# Main.net
KiCad netlist of a schematic drawn in Altium Designer
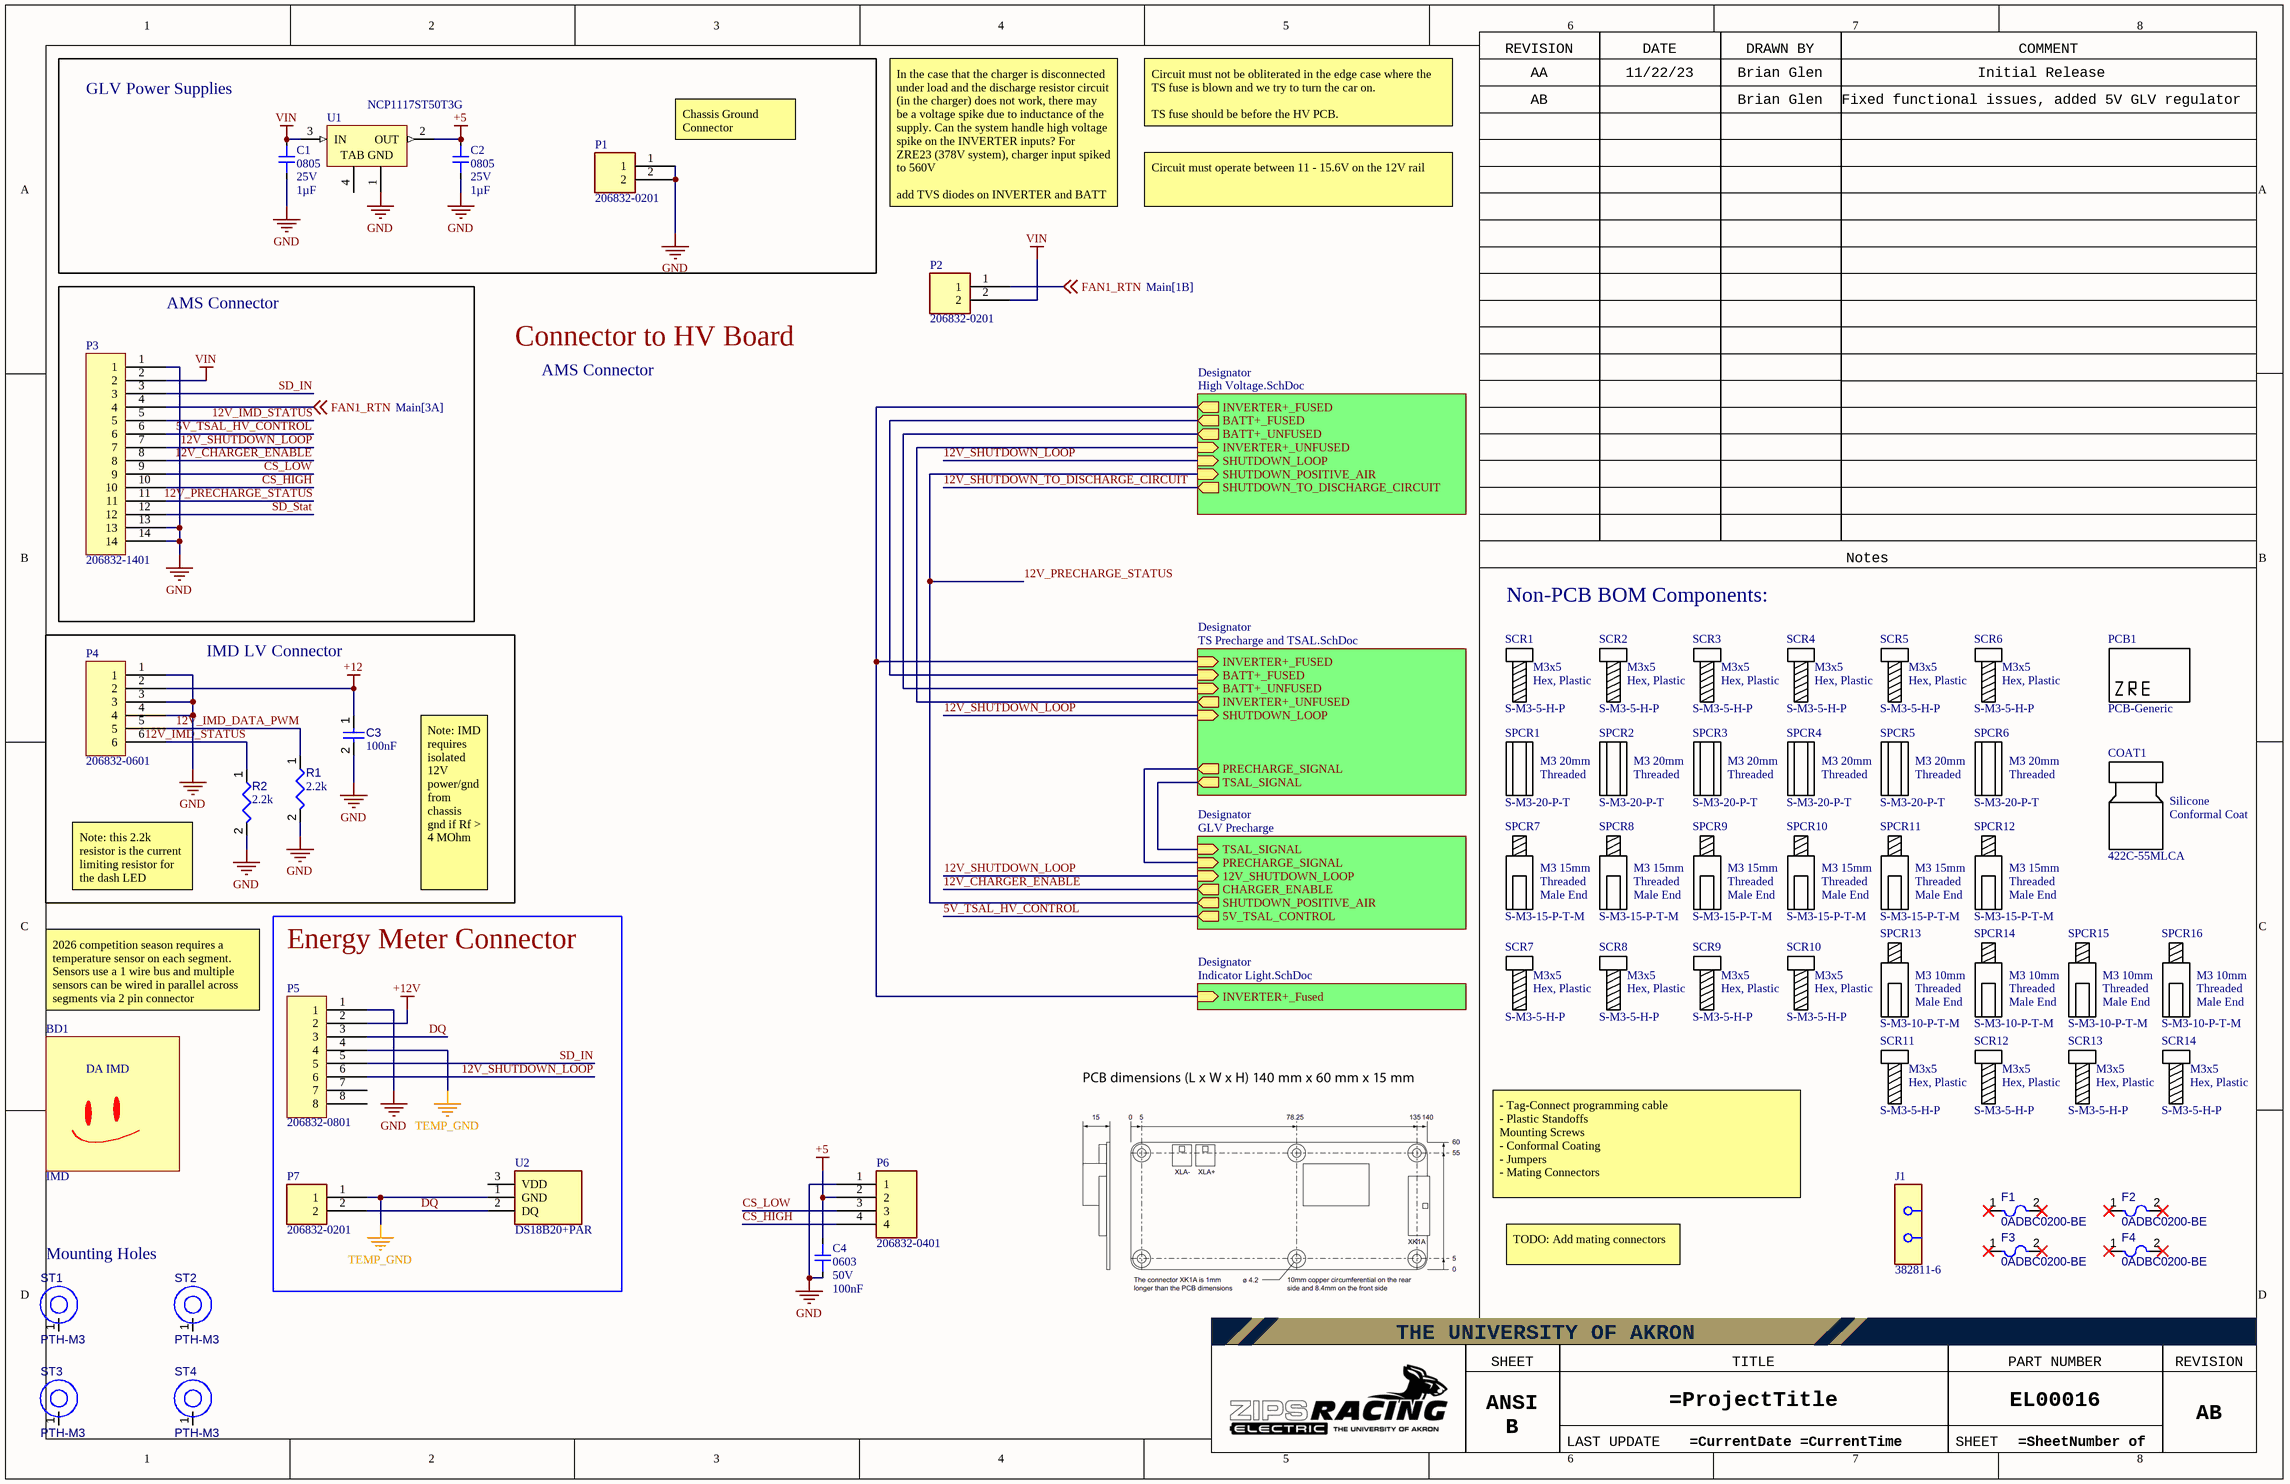
[diagram p0: Main.SchDoc]

(export (version "E")
  (design (tool "Eeschema 10.0.6"))
  (components
    (comp (ref "BD1")
      (value "IMD")
      (footprint "IMD-Footprint-1")
      (description "IMD for the CAR")
      (libsource (lib "Zips Racing Electric") (part "IMD-Symbol-1"))
    )
    (comp (ref "C1")
      (value "1µF")
      (footprint "0805")
      (description "Capacitor, 0805")
      (fields (field (name "VOLTAGE") "25V") (field (name "Comment") "Capacitor 1uF 0805 25V"))
      (libsource (lib "Zips Racing Electric") (part "CAP-0603"))
    )
    (comp (ref "C2")
      (value "1µF")
      (footprint "0805")
      (description "Capacitor, 0805")
      (fields (field (name "VOLTAGE") "25V") (field (name "Comment") "Capacitor 1uF 0805 25V"))
      (libsource (lib "Zips Racing Electric") (part "CAP-0603"))
    )
    (comp (ref "C3")
      (value "100nF")
      (footprint "CAPC1608X90X40NL10T20")
      (description "Chip Capacitor, 100 nF, +/- 10%, 50 V, 0603 (1608 Metric)")
      (fields (field (name "TOLERANCE") "10%") (field (name "Comment") "Capacitor 100 nF +/-10% 50 V 0603"))
      (libsource (lib "Zips Racing Electric") (part "CAP-NP-2"))
    )
    (comp (ref "C4")
      (value "100nF")
      (footprint "0603")
      (description "Capacitor, 0603, 5%")
      (fields (field (name "VOLTAGE") "50V") (field (name "Comment") "Capacitor 100nF 0603 5%"))
      (libsource (lib "Zips Racing Electric") (part "CAP-0603"))
    )
    (comp (ref "COAT1")
      (value "422C-55MLCA")
      (libsource (lib "Zips Racing Electric") (part "422C-55MLCA-Symbol-1"))
    )
    (comp (ref "F1")
      (value "0ADBC0200-BE")
      (description "Electric Fuse, Fast Blow, 0.2A, 1000VAC, 1000VDC, 0.2A (IR), Inline/holder, 6x32mm")
      (libsource (lib "Zips Racing Electric") (part "FUSE-2"))
    )
    (comp (ref "F2")
      (value "0ADBC0200-BE")
      (description "Electric Fuse, Fast Blow, 0.2A, 1000VAC, 1000VDC, 0.2A (IR), Inline/holder, 6x32mm")
      (libsource (lib "Zips Racing Electric") (part "FUSE-2"))
    )
    (comp (ref "F3")
      (value "0ADBC0200-BE")
      (description "Electric Fuse, Fast Blow, 0.2A, 1000VAC, 1000VDC, 0.2A (IR), Inline/holder, 6x32mm")
      (libsource (lib "Zips Racing Electric") (part "FUSE-2"))
    )
    (comp (ref "F4")
      (value "0ADBC0200-BE")
      (description "Electric Fuse, Fast Blow, 0.2A, 1000VAC, 1000VDC, 0.2A (IR), Inline/holder, 6x32mm")
      (libsource (lib "Zips Racing Electric") (part "FUSE-2"))
    )
    (comp (ref "J1")
      (value "382811-6")
      (footprint "FP-382811-6-MFG")
      (description "2-Pin Header Pin Jumper, 0.1\" pitch, Shunts/Jumper Connector")
      (libsource (lib "Zips Racing Electric") (part "9bfe63f1ac6509a30e43ee188490ecc"))
    )
    (comp (ref "P1")
      (value "206832-0201")
      (footprint "FP-206832-0201-MFG")
      (description "Molex, Micro-Fit+, 2 Position, Dual-Row, Header, Male, 3mm Pitch")
      (libsource (lib "Zips Racing Electric") (part "206832-0201"))
    )
    (comp (ref "P2")
      (value "206832-0201")
      (footprint "FP-206832-0201-MFG")
      (description "Molex, Micro-Fit+, 2 Position, Dual-Row, Header, Male, 3mm Pitch")
      (libsource (lib "Zips Racing Electric") (part "206832-0201"))
    )
    (comp (ref "P3")
      (value "206832-1401")
      (footprint "206832-1001-Footprint-1")
      (description "MICRO-FIT Plus Header Assembly Dual Row 10 Position Straight Tin")
      (libsource (lib "Zips Racing Electric") (part "206832-1401-Symbol-1"))
    )
    (comp (ref "P4")
      (value "206832-0601")
      (footprint "FP-206832-0601-MFG")
      (description "Molex, Micro-Fit+, 6 Position, Dual-Row, Header, Male, 3mm Pitch")
      (libsource (lib "Zips Racing Electric") (part "2068320601"))
    )
    (comp (ref "P5")
      (value "206832-0801")
      (footprint "Copy of 206832-1001-Footprint-1")
      (description "MICRO-FIT Plus Header Assembly Dual Row 8 Position Straight Tin")
      (libsource (lib "Zips Racing Electric") (part "206832-0801"))
    )
    (comp (ref "P6")
      (value "206832-0401")
      (footprint "MOLEX_2068320401")
      (libsource (lib "Zips Racing Electric") (part "2068320401-Symbol-1"))
    )
    (comp (ref "P7")
      (value "206832-0201")
      (footprint "FP-206832-0201-MFG")
      (description "Molex, Micro-Fit+, 2 Position, Dual-Row, Header, Male, 3mm Pitch")
      (libsource (lib "Zips Racing Electric") (part "206832-0201"))
    )
    (comp (ref "PCB1")
      (value "PCB-Generic")
      (description "Generic PCB Component for BOM inclusion")
      (libsource (lib "Zips Racing Electric") (part "PCB-Generic-Symbol-1"))
    )
    (comp (ref "R1")
      (value "2.2k")
      (footprint "RESC1608X55X25LL10T15")
      (description "Description Chip Resistor, 2.2 KOhm, +/-1%, 0.1 W, -55 to 155 degC, 0603 (1608 Metric)")
      (fields (field (name "POWER") "100mW") (field (name "TOLERANCE") "1%"))
      (libsource (lib "Zips Racing Electric") (part "RES-2"))
    )
    (comp (ref "R2")
      (value "2.2k")
      (footprint "RESC1608X55X25LL10T15")
      (description "Description Chip Resistor, 2.2 KOhm, +/-1%, 0.1 W, -55 to 155 degC, 0603 (1608 Metric)")
      (fields (field (name "POWER") "100mW") (field (name "TOLERANCE") "1%"))
      (libsource (lib "Zips Racing Electric") (part "RES-2"))
    )
    (comp (ref "SCR1")
      (value "S-M3-5-H-P")
      (description "Generic Screw, M3, 5mm length, Hex Head, Plastic")
      (libsource (lib "Zips Racing Electric") (part "S-M3-5-P-Symbol-1"))
    )
    (comp (ref "SCR2")
      (value "S-M3-5-H-P")
      (description "Generic Screw, M3, 5mm length, Hex Head, Plastic")
      (libsource (lib "Zips Racing Electric") (part "S-M3-5-P-Symbol-1"))
    )
    (comp (ref "SCR3")
      (value "S-M3-5-H-P")
      (description "Generic Screw, M3, 5mm length, Hex Head, Plastic")
      (libsource (lib "Zips Racing Electric") (part "S-M3-5-P-Symbol-1"))
    )
    (comp (ref "SCR4")
      (value "S-M3-5-H-P")
      (description "Generic Screw, M3, 5mm length, Hex Head, Plastic")
      (libsource (lib "Zips Racing Electric") (part "S-M3-5-P-Symbol-1"))
    )
    (comp (ref "SCR5")
      (value "S-M3-5-H-P")
      (description "Generic Screw, M3, 5mm length, Hex Head, Plastic")
      (libsource (lib "Zips Racing Electric") (part "S-M3-5-P-Symbol-1"))
    )
    (comp (ref "SCR6")
      (value "S-M3-5-H-P")
      (description "Generic Screw, M3, 5mm length, Hex Head, Plastic")
      (libsource (lib "Zips Racing Electric") (part "S-M3-5-P-Symbol-1"))
    )
    (comp (ref "SCR7")
      (value "S-M3-5-H-P")
      (description "Generic Screw, M3, 5mm length, Hex Head, Plastic")
      (libsource (lib "Zips Racing Electric") (part "S-M3-5-P-Symbol-1"))
    )
    (comp (ref "SCR8")
      (value "S-M3-5-H-P")
      (description "Generic Screw, M3, 5mm length, Hex Head, Plastic")
      (libsource (lib "Zips Racing Electric") (part "S-M3-5-P-Symbol-1"))
    )
    (comp (ref "SCR9")
      (value "S-M3-5-H-P")
      (description "Generic Screw, M3, 5mm length, Hex Head, Plastic")
      (libsource (lib "Zips Racing Electric") (part "S-M3-5-P-Symbol-1"))
    )
    (comp (ref "SCR10")
      (value "S-M3-5-H-P")
      (description "Generic Screw, M3, 5mm length, Hex Head, Plastic")
      (libsource (lib "Zips Racing Electric") (part "S-M3-5-P-Symbol-1"))
    )
    (comp (ref "SCR11")
      (value "S-M3-5-H-P")
      (description "Generic Screw, M3, 5mm length, Hex Head, Plastic")
      (libsource (lib "Zips Racing Electric") (part "S-M3-5-P-Symbol-1"))
    )
    (comp (ref "SCR12")
      (value "S-M3-5-H-P")
      (description "Generic Screw, M3, 5mm length, Hex Head, Plastic")
      (libsource (lib "Zips Racing Electric") (part "S-M3-5-P-Symbol-1"))
    )
    (comp (ref "SCR13")
      (value "S-M3-5-H-P")
      (description "Generic Screw, M3, 5mm length, Hex Head, Plastic")
      (libsource (lib "Zips Racing Electric") (part "S-M3-5-P-Symbol-1"))
    )
    (comp (ref "SCR14")
      (value "S-M3-5-H-P")
      (description "Generic Screw, M3, 5mm length, Hex Head, Plastic")
      (libsource (lib "Zips Racing Electric") (part "S-M3-5-P-Symbol-1"))
    )
    (comp (ref "SPCR1")
      (value "S-M3-20-P-T")
      (description "Generic M3 Spacer, 10 mm length, plastic, threaded")
      (libsource (lib "") (part "M3_Spacer_10mm_Plastic_Threaded-Symbol-1_2"))
    )
    (comp (ref "SPCR2")
      (value "S-M3-20-P-T")
      (description "Generic M3 Spacer, 10 mm length, plastic, threaded")
      (libsource (lib "") (part "M3_Spacer_10mm_Plastic_Threaded-Symbol-1_2"))
    )
    (comp (ref "SPCR3")
      (value "S-M3-20-P-T")
      (description "Generic M3 Spacer, 10 mm length, plastic, threaded")
      (libsource (lib "") (part "M3_Spacer_10mm_Plastic_Threaded-Symbol-1_2"))
    )
    (comp (ref "SPCR4")
      (value "S-M3-20-P-T")
      (description "Generic M3 Spacer, 10 mm length, plastic, threaded")
      (libsource (lib "") (part "M3_Spacer_10mm_Plastic_Threaded-Symbol-1_2"))
    )
    (comp (ref "SPCR5")
      (value "S-M3-20-P-T")
      (description "Generic M3 Spacer, 10 mm length, plastic, threaded")
      (libsource (lib "") (part "M3_Spacer_10mm_Plastic_Threaded-Symbol-1_2"))
    )
    (comp (ref "SPCR6")
      (value "S-M3-20-P-T")
      (description "Generic M3 Spacer, 10 mm length, plastic, threaded")
      (libsource (lib "") (part "M3_Spacer_10mm_Plastic_Threaded-Symbol-1_2"))
    )
    (comp (ref "SPCR7")
      (value "S-M3-15-P-T-M")
      (description "Generic M3 Spacer, 15 mm length, plastic, threaded, one male end")
      (libsource (lib "Zips Racing Electric") (part "M3_Spacer_10mm_Plastic_Threaded-Symbol-1"))
    )
    (comp (ref "SPCR8")
      (value "S-M3-15-P-T-M")
      (description "Generic M3 Spacer, 15 mm length, plastic, threaded, one male end")
      (libsource (lib "Zips Racing Electric") (part "M3_Spacer_10mm_Plastic_Threaded-Symbol-1"))
    )
    (comp (ref "SPCR9")
      (value "S-M3-15-P-T-M")
      (description "Generic M3 Spacer, 15 mm length, plastic, threaded, one male end")
      (libsource (lib "Zips Racing Electric") (part "M3_Spacer_10mm_Plastic_Threaded-Symbol-1"))
    )
    (comp (ref "SPCR10")
      (value "S-M3-15-P-T-M")
      (description "Generic M3 Spacer, 15 mm length, plastic, threaded, one male end")
      (libsource (lib "Zips Racing Electric") (part "M3_Spacer_10mm_Plastic_Threaded-Symbol-1"))
    )
    (comp (ref "SPCR11")
      (value "S-M3-15-P-T-M")
      (description "Generic M3 Spacer, 15 mm length, plastic, threaded, one male end")
      (libsource (lib "Zips Racing Electric") (part "M3_Spacer_10mm_Plastic_Threaded-Symbol-1"))
    )
    (comp (ref "SPCR12")
      (value "S-M3-15-P-T-M")
      (description "Generic M3 Spacer, 15 mm length, plastic, threaded, one male end")
      (libsource (lib "Zips Racing Electric") (part "M3_Spacer_10mm_Plastic_Threaded-Symbol-1"))
    )
    (comp (ref "SPCR13")
      (value "S-M3-10-P-T-M")
      (description "Generic M3 Spacer, 10 mm length, plastic, threaded, one male end")
      (libsource (lib "") (part "M3_Spacer_10mm_Plastic_Threaded-Symbol-1_1"))
    )
    (comp (ref "SPCR14")
      (value "S-M3-10-P-T-M")
      (description "Generic M3 Spacer, 10 mm length, plastic, threaded, one male end")
      (libsource (lib "") (part "M3_Spacer_10mm_Plastic_Threaded-Symbol-1_1"))
    )
    (comp (ref "SPCR15")
      (value "S-M3-10-P-T-M")
      (description "Generic M3 Spacer, 10 mm length, plastic, threaded, one male end")
      (libsource (lib "") (part "M3_Spacer_10mm_Plastic_Threaded-Symbol-1_1"))
    )
    (comp (ref "SPCR16")
      (value "S-M3-10-P-T-M")
      (description "Generic M3 Spacer, 10 mm length, plastic, threaded, one male end")
      (libsource (lib "") (part "M3_Spacer_10mm_Plastic_Threaded-Symbol-1_1"))
    )
    (comp (ref "ST1")
      (value "PTH-M3")
      (footprint "PTH-M2D5X5")
      (description "M3 Plated Thru-Hole  (3.2mm), 7mm pad, 10 mm keep out zone")
      (libsource (lib "Zips Racing Electric") (part "CMP-00028-00000-1"))
    )
    (comp (ref "ST2")
      (value "PTH-M3")
      (footprint "PTH-M2D5X5")
      (description "M3 Plated Thru-Hole  (3.2mm), 7mm pad, 10 mm keep out zone")
      (libsource (lib "Zips Racing Electric") (part "CMP-00028-00000-1"))
    )
    (comp (ref "ST3")
      (value "PTH-M3")
      (footprint "PTH-M2D5X5")
      (description "M3 Plated Thru-Hole  (3.2mm), 7mm pad, 10 mm keep out zone")
      (libsource (lib "Zips Racing Electric") (part "CMP-00028-00000-1"))
    )
    (comp (ref "ST4")
      (value "PTH-M3")
      (footprint "PTH-M2D5X5")
      (description "M3 Plated Thru-Hole  (3.2mm), 7mm pad, 10 mm keep out zone")
      (libsource (lib "Zips Racing Electric") (part "CMP-00028-00000-1"))
    )
    (comp (ref "U1")
      (value "NCP1117ST50T3G")
      (footprint "ONSC-SOT-223-4-318H-01_A_V")
      (fields (field (name "MANUFACTURER") "ON Semiconductor"))
      (libsource (lib "Zips Racing Electric") (part "ONSC-NCP1117ST-TO-223-4"))
    )
    (comp (ref "U2")
      (value "DS18B20+PAR")
      (footprint "New footprint 1")
      (description "Serial Switch/Digital Sensor, 12 Bit(s), 0.50Cel, Rectangular, 3 Pin, Through Hole Mount")
      (libsource (lib "Zips Racing Electric") (part "DS18B20"))
    )
  )
  (nets
    (net (code "1") (name "+5") (class "Default")
      (node (ref "C2") (pin "2") (pinfunction "2_2") (pintype "passive"))
      (node (ref "C4") (pin "2") (pinfunction "2_2") (pintype "passive"))
      (node (ref "P6") (pin "2") (pinfunction "2_2") (pintype "passive"))
      (node (ref "U1") (pin "2") (pinfunction "OUT_2") (pintype "output"))
    )
    (net (code "2") (name "+12") (class "Default")
      (node (ref "C3") (pin "1") (pinfunction "1_1") (pintype "passive"))
      (node (ref "P4") (pin "2") (pinfunction "2_2") (pintype "passive"))
    )
    (net (code "3") (name "+12V") (class "Default")
      (node (ref "P5") (pin "2") (pinfunction "2_2") (pintype "passive"))
    )
    (net (code "4") (name "/5V_TSAL_HV_CONTROL") (class "Default")
      (node (ref "P3") (pin "6") (pinfunction "6_6") (pintype "passive"))
    )
    (net (code "5") (name "/12V_CHARGER_ENABLE") (class "Default")
      (node (ref "P3") (pin "8") (pinfunction "8_8") (pintype "passive"))
    )
    (net (code "6") (name "/12V_IMD_DATA_PWM") (class "Default")
      (node (ref "P4") (pin "5") (pinfunction "5_5") (pintype "passive"))
      (node (ref "R1") (pin "1") (pinfunction "1_1") (pintype "passive"))
    )
    (net (code "7") (name "/12V_IMD_STATUS") (class "Default")
      (node (ref "P3") (pin "5") (pinfunction "5_5") (pintype "passive"))
      (node (ref "P4") (pin "6") (pinfunction "6_6") (pintype "passive"))
      (node (ref "R2") (pin "1") (pinfunction "1_1") (pintype "passive"))
    )
    (net (code "8") (name "/12V_PRECHARGE_STATUS") (class "Default")
      (node (ref "P3") (pin "11") (pinfunction "11_11") (pintype "passive"))
    )
    (net (code "9") (name "/12V_SHUTDOWN_LOOP") (class "Default")
      (node (ref "P3") (pin "7") (pinfunction "7_7") (pintype "passive"))
      (node (ref "P5") (pin "6") (pinfunction "6_6") (pintype "passive"))
    )
    (net (code "13") (name "/CS_HIGH") (class "Default")
      (node (ref "P3") (pin "10") (pinfunction "10_10") (pintype "passive"))
      (node (ref "P6") (pin "4") (pinfunction "4_4") (pintype "passive"))
    )
    (net (code "14") (name "/CS_LOW") (class "Default")
      (node (ref "P3") (pin "9") (pinfunction "9_9") (pintype "passive"))
      (node (ref "P6") (pin "3") (pinfunction "3_3") (pintype "passive"))
    )
    (net (code "15") (name "/DQ") (class "Default")
      (node (ref "P5") (pin "3") (pinfunction "3_3") (pintype "passive"))
      (node (ref "P7") (pin "2") (pinfunction "2_2") (pintype "passive"))
      (node (ref "U2") (pin "2") (pinfunction "DQ_2") (pintype "passive"))
    )
    (net (code "19") (name "/SD_IN") (class "Default")
      (node (ref "P3") (pin "3") (pinfunction "3_3") (pintype "passive"))
      (node (ref "P5") (pin "5") (pinfunction "5_5") (pintype "passive"))
    )
    (net (code "20") (name "/SD_Stat") (class "Default")
      (node (ref "P3") (pin "12") (pinfunction "12_12") (pintype "passive"))
    )
    (net (code "22") (name "FAN1_RTN") (class "Default")
      (node (ref "P2") (pin "1") (pinfunction "1_1") (pintype "passive"))
      (node (ref "P3") (pin "4") (pinfunction "4_4") (pintype "passive"))
    )
    (net (code "23") (name "GND") (class "Default")
      (node (ref "C1") (pin "1") (pinfunction "1_1") (pintype "passive"))
      (node (ref "C2") (pin "1") (pinfunction "1_1") (pintype "passive"))
      (node (ref "C3") (pin "2") (pinfunction "2_2") (pintype "passive"))
      (node (ref "C4") (pin "1") (pinfunction "1_1") (pintype "passive"))
      (node (ref "P1") (pin "1") (pinfunction "1_1") (pintype "passive"))
      (node (ref "P1") (pin "2") (pinfunction "2_2") (pintype "passive"))
      (node (ref "P3") (pin "1") (pinfunction "1_1") (pintype "passive"))
      (node (ref "P3") (pin "13") (pinfunction "13_13") (pintype "passive"))
      (node (ref "P3") (pin "14") (pinfunction "14_14") (pintype "passive"))
      (node (ref "P4") (pin "1") (pinfunction "1_1") (pintype "passive"))
      (node (ref "P4") (pin "3") (pinfunction "3_3") (pintype "passive"))
      (node (ref "P4") (pin "4") (pinfunction "4_4") (pintype "passive"))
      (node (ref "P5") (pin "1") (pinfunction "1_1") (pintype "passive"))
      (node (ref "P6") (pin "1") (pinfunction "1_1") (pintype "passive"))
      (node (ref "R1") (pin "2") (pinfunction "2_2") (pintype "passive"))
      (node (ref "R2") (pin "2") (pinfunction "2_2") (pintype "passive"))
      (node (ref "U1") (pin "1") (pinfunction "GND_1") (pintype "power_in"))
    )
    (net (code "24") (name "TEMP_GND") (class "Default")
      (node (ref "P5") (pin "4") (pinfunction "4_4") (pintype "passive"))
      (node (ref "P7") (pin "1") (pinfunction "1_1") (pintype "passive"))
      (node (ref "U2") (pin "1") (pinfunction "GND_1") (pintype "power_in"))
    )
    (net (code "25") (name "VIN") (class "Default")
      (node (ref "C1") (pin "2") (pinfunction "2_2") (pintype "passive"))
      (node (ref "P2") (pin "2") (pinfunction "2_2") (pintype "passive"))
      (node (ref "P3") (pin "2") (pinfunction "2_2") (pintype "passive"))
      (node (ref "U1") (pin "3") (pinfunction "IN_3") (pintype "input"))
    )
    (net (code "26") (name "unconnected-(F1-Pad1)") (class "Default")
      (node (ref "F1") (pin "1") (pinfunction "1_1") (pintype "passive+no_connect"))
    )
    (net (code "27") (name "unconnected-(F1-Pad2)") (class "Default")
      (node (ref "F1") (pin "2") (pinfunction "2_2") (pintype "passive+no_connect"))
    )
    (net (code "28") (name "unconnected-(F2-Pad1)") (class "Default")
      (node (ref "F2") (pin "1") (pinfunction "1_1") (pintype "passive+no_connect"))
    )
    (net (code "29") (name "unconnected-(F2-Pad2)") (class "Default")
      (node (ref "F2") (pin "2") (pinfunction "2_2") (pintype "passive+no_connect"))
    )
    (net (code "30") (name "unconnected-(F3-Pad1)") (class "Default")
      (node (ref "F3") (pin "1") (pinfunction "1_1") (pintype "passive+no_connect"))
    )
    (net (code "31") (name "unconnected-(F3-Pad2)") (class "Default")
      (node (ref "F3") (pin "2") (pinfunction "2_2") (pintype "passive+no_connect"))
    )
    (net (code "32") (name "unconnected-(F4-Pad1)") (class "Default")
      (node (ref "F4") (pin "1") (pinfunction "1_1") (pintype "passive+no_connect"))
    )
    (net (code "33") (name "unconnected-(F4-Pad2)") (class "Default")
      (node (ref "F4") (pin "2") (pinfunction "2_2") (pintype "passive+no_connect"))
    )
    (net (code "34") (name "unconnected-(P5-Pad7)") (class "Default")
      (node (ref "P5") (pin "7") (pinfunction "7_7") (pintype "passive"))
    )
    (net (code "35") (name "unconnected-(P5-Pad8)") (class "Default")
      (node (ref "P5") (pin "8") (pinfunction "8_8") (pintype "passive"))
    )
    (net (code "36") (name "unconnected-(ST1-H1-Pad1)") (class "Default")
      (node (ref "ST1") (pin "1") (pinfunction "H1_1") (pintype "passive"))
    )
    (net (code "37") (name "unconnected-(ST2-H1-Pad1)") (class "Default")
      (node (ref "ST2") (pin "1") (pinfunction "H1_1") (pintype "passive"))
    )
    (net (code "38") (name "unconnected-(ST3-H1-Pad1)") (class "Default")
      (node (ref "ST3") (pin "1") (pinfunction "H1_1") (pintype "passive"))
    )
    (net (code "39") (name "unconnected-(ST4-H1-Pad1)") (class "Default")
      (node (ref "ST4") (pin "1") (pinfunction "H1_1") (pintype "passive"))
    )
    (net (code "40") (name "unconnected-(U1-TAB-Pad4)") (class "Default")
      (node (ref "U1") (pin "4") (pinfunction "TAB_4") (pintype "power_in"))
    )
    (net (code "41") (name "unconnected-(U2-VDD-Pad3)") (class "Default")
      (node (ref "U2") (pin "3") (pinfunction "VDD_3") (pintype "power_in"))
    )
  )
)
